# 5_RK3399_EDP_CSI_HDMI.net
KiCad netlist of a schematic drawn in Altium Designer
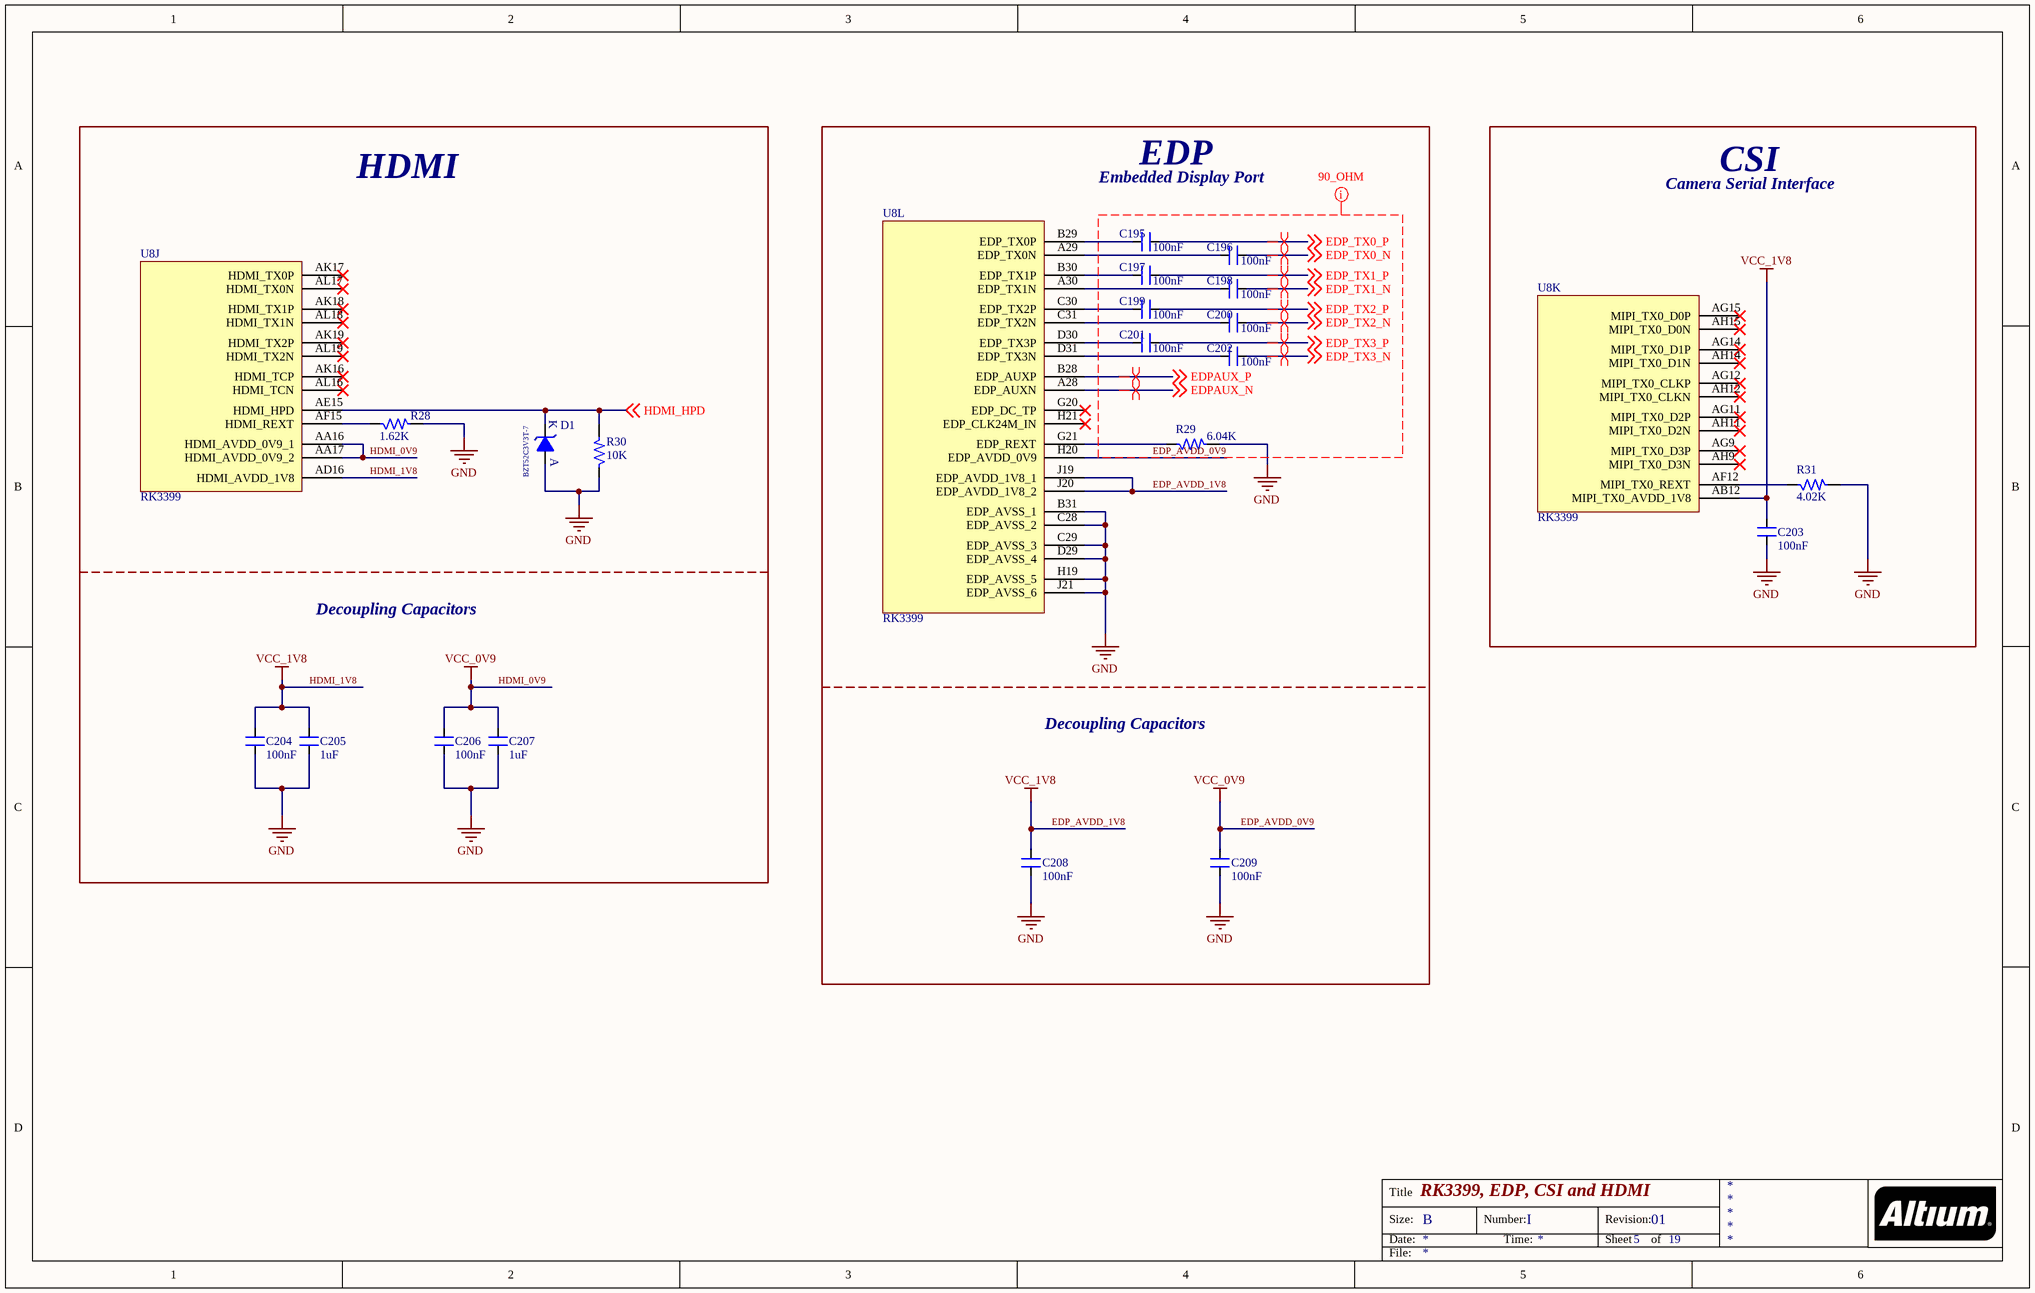
[diagram p0: [5] RK3399_EDP_CSI_HDMI.SchDoc]

(export (version "E")
  (design (tool "Eeschema 10.0.6"))
  (components
    (comp (ref "C195")
      (value "100nF")
      (footprint "CAP_0201")
      (description "0.1µF ±10% 25V Ceramic Capacitor X5R 0201 (0603 Metric)")
      (fields
        (field (name "MANUFACTURER") "TDK Corporation")
        (field (name "MANUFACTURER PART NUMBER") "C0603X5R1E104K030BB")
      )
      (libsource (lib "EsteemPCB_SOM_Course_intlib") (part "CAP_100nF-25V-10%-0201"))
    )
    (comp (ref "C196")
      (value "100nF")
      (footprint "CAP_0201")
      (description "0.1µF ±10% 25V Ceramic Capacitor X5R 0201 (0603 Metric)")
      (fields
        (field (name "MANUFACTURER") "TDK Corporation")
        (field (name "MANUFACTURER PART NUMBER") "C0603X5R1E104K030BB")
      )
      (libsource (lib "EsteemPCB_SOM_Course_intlib") (part "CAP_100nF-25V-10%-0201"))
    )
    (comp (ref "C197")
      (value "100nF")
      (footprint "CAP_0201")
      (description "0.1µF ±10% 25V Ceramic Capacitor X5R 0201 (0603 Metric)")
      (fields
        (field (name "MANUFACTURER") "TDK Corporation")
        (field (name "MANUFACTURER PART NUMBER") "C0603X5R1E104K030BB")
      )
      (libsource (lib "EsteemPCB_SOM_Course_intlib") (part "CAP_100nF-25V-10%-0201"))
    )
    (comp (ref "C198")
      (value "100nF")
      (footprint "CAP_0201")
      (description "0.1µF ±10% 25V Ceramic Capacitor X5R 0201 (0603 Metric)")
      (fields
        (field (name "MANUFACTURER") "TDK Corporation")
        (field (name "MANUFACTURER PART NUMBER") "C0603X5R1E104K030BB")
      )
      (libsource (lib "EsteemPCB_SOM_Course_intlib") (part "CAP_100nF-25V-10%-0201"))
    )
    (comp (ref "C199")
      (value "100nF")
      (footprint "CAP_0201")
      (description "0.1µF ±10% 25V Ceramic Capacitor X5R 0201 (0603 Metric)")
      (fields
        (field (name "MANUFACTURER") "TDK Corporation")
        (field (name "MANUFACTURER PART NUMBER") "C0603X5R1E104K030BB")
      )
      (libsource (lib "EsteemPCB_SOM_Course_intlib") (part "CAP_100nF-25V-10%-0201"))
    )
    (comp (ref "C200")
      (value "100nF")
      (footprint "CAP_0201")
      (description "0.1µF ±10% 25V Ceramic Capacitor X5R 0201 (0603 Metric)")
      (fields
        (field (name "MANUFACTURER") "TDK Corporation")
        (field (name "MANUFACTURER PART NUMBER") "C0603X5R1E104K030BB")
      )
      (libsource (lib "EsteemPCB_SOM_Course_intlib") (part "CAP_100nF-25V-10%-0201"))
    )
    (comp (ref "C201")
      (value "100nF")
      (footprint "CAP_0201")
      (description "0.1µF ±10% 25V Ceramic Capacitor X5R 0201 (0603 Metric)")
      (fields
        (field (name "MANUFACTURER") "TDK Corporation")
        (field (name "MANUFACTURER PART NUMBER") "C0603X5R1E104K030BB")
      )
      (libsource (lib "EsteemPCB_SOM_Course_intlib") (part "CAP_100nF-25V-10%-0201"))
    )
    (comp (ref "C202")
      (value "100nF")
      (footprint "CAP_0201")
      (description "0.1µF ±10% 25V Ceramic Capacitor X5R 0201 (0603 Metric)")
      (fields
        (field (name "MANUFACTURER") "TDK Corporation")
        (field (name "MANUFACTURER PART NUMBER") "C0603X5R1E104K030BB")
      )
      (libsource (lib "EsteemPCB_SOM_Course_intlib") (part "CAP_100nF-25V-10%-0201"))
    )
    (comp (ref "C203")
      (value "100nF")
      (footprint "CAP_0201")
      (description "0.1µF ±10% 25V Ceramic Capacitor X5R 0201 (0603 Metric)")
      (fields
        (field (name "MANUFACTURER") "TDK Corporation")
        (field (name "MANUFACTURER PART NUMBER") "C0603X5R1E104K030BB")
      )
      (libsource (lib "EsteemPCB_SOM_Course_intlib") (part "CAP_100nF-25V-10%-0201"))
    )
    (comp (ref "C204")
      (value "100nF")
      (footprint "CAP_0201")
      (description "0.1µF ±10% 25V Ceramic Capacitor X5R 0201 (0603 Metric)")
      (fields
        (field (name "MANUFACTURER") "TDK Corporation")
        (field (name "MANUFACTURER PART NUMBER") "C0603X5R1E104K030BB")
      )
      (libsource (lib "EsteemPCB_SOM_Course_intlib") (part "CAP_100nF-25V-10%-0201"))
    )
    (comp (ref "C205")
      (value "1uF")
      (footprint "CAP_0201")
      (description "1µF ±20% 16V Ceramic Capacitor X5R 0201 (0603 Metric)")
      (fields
        (field (name "MANUFACTURER") "Samsung Electro-Mechanics")
        (field (name "MANUFACTURER PART NUMBER") "CL03A105MO3NRNH")
      )
      (libsource (lib "EsteemPCB_SOM_Course_intlib") (part "CAP_1uF-16V-10%-0201"))
    )
    (comp (ref "C206")
      (value "100nF")
      (footprint "CAP_0201")
      (description "0.1µF ±10% 25V Ceramic Capacitor X5R 0201 (0603 Metric)")
      (fields
        (field (name "MANUFACTURER") "TDK Corporation")
        (field (name "MANUFACTURER PART NUMBER") "C0603X5R1E104K030BB")
      )
      (libsource (lib "EsteemPCB_SOM_Course_intlib") (part "CAP_100nF-25V-10%-0201"))
    )
    (comp (ref "C207")
      (value "1uF")
      (footprint "CAP_0201")
      (description "1µF ±20% 16V Ceramic Capacitor X5R 0201 (0603 Metric)")
      (fields
        (field (name "MANUFACTURER") "Samsung Electro-Mechanics")
        (field (name "MANUFACTURER PART NUMBER") "CL03A105MO3NRNH")
      )
      (libsource (lib "EsteemPCB_SOM_Course_intlib") (part "CAP_1uF-16V-10%-0201"))
    )
    (comp (ref "C208")
      (value "100nF")
      (footprint "CAP_0201")
      (description "0.1µF ±10% 25V Ceramic Capacitor X5R 0201 (0603 Metric)")
      (fields
        (field (name "MANUFACTURER") "TDK Corporation")
        (field (name "MANUFACTURER PART NUMBER") "C0603X5R1E104K030BB")
      )
      (libsource (lib "EsteemPCB_SOM_Course_intlib") (part "CAP_100nF-25V-10%-0201"))
    )
    (comp (ref "C209")
      (value "100nF")
      (footprint "CAP_0201")
      (description "0.1µF ±10% 25V Ceramic Capacitor X5R 0201 (0603 Metric)")
      (fields
        (field (name "MANUFACTURER") "TDK Corporation")
        (field (name "MANUFACTURER PART NUMBER") "C0603X5R1E104K030BB")
      )
      (libsource (lib "EsteemPCB_SOM_Course_intlib") (part "CAP_100nF-25V-10%-0201"))
    )
    (comp (ref "D1")
      (value "BZT52C3V3T-7")
      (footprint "DIO_SOD523")
      (description "Zener Diode 3.3V 300mW ±6% Surface Mount SOD-523")
      (fields (field (name "MANUFACTURER") "Diodes Incorporated"))
      (libsource (lib "EsteemPCB_SOM_Course_intlib") (part "DIO-Z_3.3V-300mW-SOD-523"))
    )
    (comp (ref "R28")
      (value "1.62K")
      (footprint "RES_0201")
      (description "1.62 kOhms ±1% 0.05W, 1/20W Chip Resistor 0201 (0603 Metric) Automotive AEC-Q200 Thick Film")
      (fields
        (field (name "MANUFACTURER") "Panasonic Electronic Components")
        (field (name "MANUFACTURER PART NUMBER") "ERJ-1GNF1621C")
      )
      (libsource (lib "EsteemPCB_SOM_Course_intlib") (part "RES_1.62K-0.05W-1%-0201"))
    )
    (comp (ref "R29")
      (value "6.04K")
      (footprint "RES_0201")
      (description "6.04 kOhms ±1% 0.05W, 1/20W Chip Resistor 0201 (0603 Metric) Thick Film")
      (fields
        (field (name "MANUFACTURER") "Panasonic Electronic Components")
        (field (name "MANUFACTURER PART NUMBER") "ERJ-1GEF6041C")
      )
      (libsource (lib "EsteemPCB_SOM_Course_intlib") (part "RES_6.04K-0.05W-1%-0201"))
    )
    (comp (ref "R30")
      (value "10K")
      (footprint "RES_0201")
      (description "10 kOhms ±1% 0.05W, 1/20W Chip Resistor 0201 (0603 Metric) Thick Film")
      (fields
        (field (name "MANUFACTURER") "Stackpole Electronics Inc")
        (field (name "MANUFACTURER PART NUMBER") "RMCF0201FT10K0")
      )
      (libsource (lib "EsteemPCB_SOM_Course_intlib") (part "RES_10K-0.05W-1%-0201"))
    )
    (comp (ref "R31")
      (value "4.02K")
      (footprint "RES_0201")
      (description "4.02 kOhms ±1% 0.05W, 1/20W Chip Resistor 0201 (0603 Metric) Thick Film")
      (fields
        (field (name "MANUFACTURER") "Yageo")
        (field (name "MANUFACTURER PART NUMBER") "RC0201FR-074K02L")
      )
      (libsource (lib "EsteemPCB_SOM_Course_intlib") (part "RES_4.02K-0.05W-1%-0201"))
    )
    (comp (ref "U8")
      (value "RK3399")
      (footprint "FBGA828_23_826X826")
      (description "RK3399 is a low power, high performance processor for computing, personal mobile.")
      (fields (field (name "MANUFACTURER") "Rockchip"))
      (libsource (lib "EsteemPCB_SOM_Course_intlib") (part "IC_RK3399-FCBGA828"))
    )
  )
  (nets
    (net (code "1") (name "EDPAUX_N") (class "Default")
      (node (ref "U8") (pin "A28") (pinfunction "EDP_AUXN_A28") (pintype "passive"))
    )
    (net (code "2") (name "EDPAUX_P") (class "Default")
      (node (ref "U8") (pin "B28") (pinfunction "EDP_AUXP_B28") (pintype "passive"))
    )
    (net (code "3") (name "EDP_TX0_N") (class "Default")
      (node (ref "C196") (pin "2") (pinfunction "2_2") (pintype "passive"))
    )
    (net (code "4") (name "EDP_TX0_P") (class "Default")
      (node (ref "C195") (pin "2") (pinfunction "2_2") (pintype "passive"))
    )
    (net (code "5") (name "EDP_TX1_N") (class "Default")
      (node (ref "C198") (pin "2") (pinfunction "2_2") (pintype "passive"))
    )
    (net (code "6") (name "EDP_TX1_P") (class "Default")
      (node (ref "C197") (pin "2") (pinfunction "2_2") (pintype "passive"))
    )
    (net (code "7") (name "EDP_TX2_N") (class "Default")
      (node (ref "C200") (pin "2") (pinfunction "2_2") (pintype "passive"))
    )
    (net (code "8") (name "EDP_TX2_P") (class "Default")
      (node (ref "C199") (pin "2") (pinfunction "2_2") (pintype "passive"))
    )
    (net (code "9") (name "EDP_TX3_N") (class "Default")
      (node (ref "C202") (pin "2") (pinfunction "2_2") (pintype "passive"))
    )
    (net (code "10") (name "EDP_TX3_P") (class "Default")
      (node (ref "C201") (pin "2") (pinfunction "2_2") (pintype "passive"))
    )
    (net (code "11") (name "GND") (class "Default")
      (node (ref "C203") (pin "1") (pinfunction "1_1") (pintype "passive"))
      (node (ref "C204") (pin "1") (pinfunction "1_1") (pintype "passive"))
      (node (ref "C205") (pin "1") (pinfunction "1_1") (pintype "passive"))
      (node (ref "C206") (pin "1") (pinfunction "1_1") (pintype "passive"))
      (node (ref "C207") (pin "1") (pinfunction "1_1") (pintype "passive"))
      (node (ref "C208") (pin "1") (pinfunction "1_1") (pintype "passive"))
      (node (ref "C209") (pin "1") (pinfunction "1_1") (pintype "passive"))
      (node (ref "D1") (pin "A") (pinfunction "A_A") (pintype "passive"))
      (node (ref "R28") (pin "2") (pinfunction "2_2") (pintype "passive"))
      (node (ref "R29") (pin "2") (pinfunction "2_2") (pintype "passive"))
      (node (ref "R30") (pin "1") (pinfunction "1_1") (pintype "passive"))
      (node (ref "R31") (pin "2") (pinfunction "2_2") (pintype "passive"))
      (node (ref "U8") (pin "B31") (pinfunction "EDP_AVSS_1_B31") (pintype "passive"))
      (node (ref "U8") (pin "C28") (pinfunction "EDP_AVSS_2_C28") (pintype "passive"))
      (node (ref "U8") (pin "C29") (pinfunction "EDP_AVSS_3_C29") (pintype "passive"))
      (node (ref "U8") (pin "D29") (pinfunction "EDP_AVSS_4_D29") (pintype "passive"))
      (node (ref "U8") (pin "H19") (pinfunction "EDP_AVSS_5_H19") (pintype "passive"))
      (node (ref "U8") (pin "J21") (pinfunction "EDP_AVSS_6_J21") (pintype "passive"))
    )
    (net (code "12") (name "HDMI_HPD") (class "Default")
      (node (ref "D1") (pin "K") (pinfunction "K_K") (pintype "passive"))
      (node (ref "R30") (pin "2") (pinfunction "2_2") (pintype "passive"))
      (node (ref "U8") (pin "AE15") (pinfunction "HDMI_HPD_AE15") (pintype "passive"))
    )
    (net (code "13") (name "Net-(U8J-HDMI_REXT)") (class "Default")
      (node (ref "R28") (pin "1") (pinfunction "1_1") (pintype "passive"))
      (node (ref "U8") (pin "AF15") (pinfunction "HDMI_REXT_AF15") (pintype "passive"))
    )
    (net (code "14") (name "Net-(U8K-MIPI_TX0_REXT)") (class "Default")
      (node (ref "R31") (pin "1") (pinfunction "1_1") (pintype "passive"))
      (node (ref "U8") (pin "AF12") (pinfunction "MIPI_TX0_REXT_AF12") (pintype "passive"))
    )
    (net (code "15") (name "Net-(U8L-EDP_REXT)") (class "Default")
      (node (ref "R29") (pin "1") (pinfunction "1_1") (pintype "passive"))
      (node (ref "U8") (pin "G21") (pinfunction "EDP_REXT_G21") (pintype "passive"))
    )
    (net (code "16") (name "Net-(U8L-EDP_TX0N)") (class "Default")
      (node (ref "C196") (pin "1") (pinfunction "1_1") (pintype "passive"))
      (node (ref "U8") (pin "A29") (pinfunction "EDP_TX0N_A29") (pintype "passive"))
    )
    (net (code "17") (name "Net-(U8L-EDP_TX0P)") (class "Default")
      (node (ref "C195") (pin "1") (pinfunction "1_1") (pintype "passive"))
      (node (ref "U8") (pin "B29") (pinfunction "EDP_TX0P_B29") (pintype "passive"))
    )
    (net (code "18") (name "Net-(U8L-EDP_TX1N)") (class "Default")
      (node (ref "C198") (pin "1") (pinfunction "1_1") (pintype "passive"))
      (node (ref "U8") (pin "A30") (pinfunction "EDP_TX1N_A30") (pintype "passive"))
    )
    (net (code "19") (name "Net-(U8L-EDP_TX1P)") (class "Default")
      (node (ref "C197") (pin "1") (pinfunction "1_1") (pintype "passive"))
      (node (ref "U8") (pin "B30") (pinfunction "EDP_TX1P_B30") (pintype "passive"))
    )
    (net (code "20") (name "Net-(U8L-EDP_TX2N)") (class "Default")
      (node (ref "C200") (pin "1") (pinfunction "1_1") (pintype "passive"))
      (node (ref "U8") (pin "C31") (pinfunction "EDP_TX2N_C31") (pintype "passive"))
    )
    (net (code "21") (name "Net-(U8L-EDP_TX2P)") (class "Default")
      (node (ref "C199") (pin "1") (pinfunction "1_1") (pintype "passive"))
      (node (ref "U8") (pin "C30") (pinfunction "EDP_TX2P_C30") (pintype "passive"))
    )
    (net (code "22") (name "Net-(U8L-EDP_TX3N)") (class "Default")
      (node (ref "C202") (pin "1") (pinfunction "1_1") (pintype "passive"))
      (node (ref "U8") (pin "D31") (pinfunction "EDP_TX3N_D31") (pintype "passive"))
    )
    (net (code "23") (name "Net-(U8L-EDP_TX3P)") (class "Default")
      (node (ref "C201") (pin "1") (pinfunction "1_1") (pintype "passive"))
      (node (ref "U8") (pin "D30") (pinfunction "EDP_TX3P_D30") (pintype "passive"))
    )
    (net (code "24") (name "VCC_0V9") (class "Default")
      (node (ref "C206") (pin "2") (pinfunction "2_2") (pintype "passive"))
      (node (ref "C207") (pin "2") (pinfunction "2_2") (pintype "passive"))
      (node (ref "C209") (pin "2") (pinfunction "2_2") (pintype "passive"))
      (node (ref "U8") (pin "AA16") (pinfunction "HDMI_AVDD_0V9_1_AA16") (pintype "passive"))
      (node (ref "U8") (pin "AA17") (pinfunction "HDMI_AVDD_0V9_2_AA17") (pintype "passive"))
      (node (ref "U8") (pin "H20") (pinfunction "EDP_AVDD_0V9_H20") (pintype "passive"))
    )
    (net (code "25") (name "VCC_1V8") (class "Default")
      (node (ref "C203") (pin "2") (pinfunction "2_2") (pintype "passive"))
      (node (ref "C204") (pin "2") (pinfunction "2_2") (pintype "passive"))
      (node (ref "C205") (pin "2") (pinfunction "2_2") (pintype "passive"))
      (node (ref "C208") (pin "2") (pinfunction "2_2") (pintype "passive"))
      (node (ref "U8") (pin "AB12") (pinfunction "MIPI_TX0_AVDD_1V8_AB12") (pintype "passive"))
      (node (ref "U8") (pin "AD16") (pinfunction "HDMI_AVDD_1V8_AD16") (pintype "passive"))
      (node (ref "U8") (pin "J19") (pinfunction "EDP_AVDD_1V8_1_J19") (pintype "passive"))
      (node (ref "U8") (pin "J20") (pinfunction "EDP_AVDD_1V8_2_J20") (pintype "passive"))
    )
    (net (code "26") (name "unconnected-(U8J-HDMI_TCN-PadAL16)") (class "Default")
      (node (ref "U8") (pin "AL16") (pinfunction "HDMI_TCN_AL16") (pintype "passive+no_connect"))
    )
    (net (code "27") (name "unconnected-(U8J-HDMI_TCP-PadAK16)") (class "Default")
      (node (ref "U8") (pin "AK16") (pinfunction "HDMI_TCP_AK16") (pintype "passive+no_connect"))
    )
    (net (code "28") (name "unconnected-(U8J-HDMI_TX0N-PadAL17)") (class "Default")
      (node (ref "U8") (pin "AL17") (pinfunction "HDMI_TX0N_AL17") (pintype "passive+no_connect"))
    )
    (net (code "29") (name "unconnected-(U8J-HDMI_TX0P-PadAK17)") (class "Default")
      (node (ref "U8") (pin "AK17") (pinfunction "HDMI_TX0P_AK17") (pintype "passive+no_connect"))
    )
    (net (code "30") (name "unconnected-(U8J-HDMI_TX1N-PadAL18)") (class "Default")
      (node (ref "U8") (pin "AL18") (pinfunction "HDMI_TX1N_AL18") (pintype "passive+no_connect"))
    )
    (net (code "31") (name "unconnected-(U8J-HDMI_TX1P-PadAK18)") (class "Default")
      (node (ref "U8") (pin "AK18") (pinfunction "HDMI_TX1P_AK18") (pintype "passive+no_connect"))
    )
    (net (code "32") (name "unconnected-(U8J-HDMI_TX2N-PadAL19)") (class "Default")
      (node (ref "U8") (pin "AL19") (pinfunction "HDMI_TX2N_AL19") (pintype "passive+no_connect"))
    )
    (net (code "33") (name "unconnected-(U8J-HDMI_TX2P-PadAK19)") (class "Default")
      (node (ref "U8") (pin "AK19") (pinfunction "HDMI_TX2P_AK19") (pintype "passive+no_connect"))
    )
    (net (code "34") (name "unconnected-(U8K-MIPI_TX0_CLKN-PadAH12)") (class "Default")
      (node (ref "U8") (pin "AH12") (pinfunction "MIPI_TX0_CLKN_AH12") (pintype "passive+no_connect"))
    )
    (net (code "35") (name "unconnected-(U8K-MIPI_TX0_CLKP-PadAG12)") (class "Default")
      (node (ref "U8") (pin "AG12") (pinfunction "MIPI_TX0_CLKP_AG12") (pintype "passive+no_connect"))
    )
    (net (code "36") (name "unconnected-(U8K-MIPI_TX0_D0N-PadAH15)") (class "Default")
      (node (ref "U8") (pin "AH15") (pinfunction "MIPI_TX0_D0N_AH15") (pintype "passive+no_connect"))
    )
    (net (code "37") (name "unconnected-(U8K-MIPI_TX0_D0P-PadAG15)") (class "Default")
      (node (ref "U8") (pin "AG15") (pinfunction "MIPI_TX0_D0P_AG15") (pintype "passive+no_connect"))
    )
    (net (code "38") (name "unconnected-(U8K-MIPI_TX0_D1N-PadAH14)") (class "Default")
      (node (ref "U8") (pin "AH14") (pinfunction "MIPI_TX0_D1N_AH14") (pintype "passive+no_connect"))
    )
    (net (code "39") (name "unconnected-(U8K-MIPI_TX0_D1P-PadAG14)") (class "Default")
      (node (ref "U8") (pin "AG14") (pinfunction "MIPI_TX0_D1P_AG14") (pintype "passive+no_connect"))
    )
    (net (code "40") (name "unconnected-(U8K-MIPI_TX0_D2N-PadAH11)") (class "Default")
      (node (ref "U8") (pin "AH11") (pinfunction "MIPI_TX0_D2N_AH11") (pintype "passive+no_connect"))
    )
    (net (code "41") (name "unconnected-(U8K-MIPI_TX0_D2P-PadAG11)") (class "Default")
      (node (ref "U8") (pin "AG11") (pinfunction "MIPI_TX0_D2P_AG11") (pintype "passive+no_connect"))
    )
    (net (code "42") (name "unconnected-(U8K-MIPI_TX0_D3N-PadAH9)") (class "Default")
      (node (ref "U8") (pin "AH9") (pinfunction "MIPI_TX0_D3N_AH9") (pintype "passive+no_connect"))
    )
    (net (code "43") (name "unconnected-(U8K-MIPI_TX0_D3P-PadAG9)") (class "Default")
      (node (ref "U8") (pin "AG9") (pinfunction "MIPI_TX0_D3P_AG9") (pintype "passive+no_connect"))
    )
    (net (code "44") (name "unconnected-(U8L-EDP_CLK24M_IN-PadH21)") (class "Default")
      (node (ref "U8") (pin "H21") (pinfunction "EDP_CLK24M_IN_H21") (pintype "passive+no_connect"))
    )
    (net (code "45") (name "unconnected-(U8L-EDP_DC_TP-PadG20)") (class "Default")
      (node (ref "U8") (pin "G20") (pinfunction "EDP_DC_TP_G20") (pintype "passive+no_connect"))
    )
  )
)
